# burn.net
KiCad netlist of a schematic drawn in EAGLE
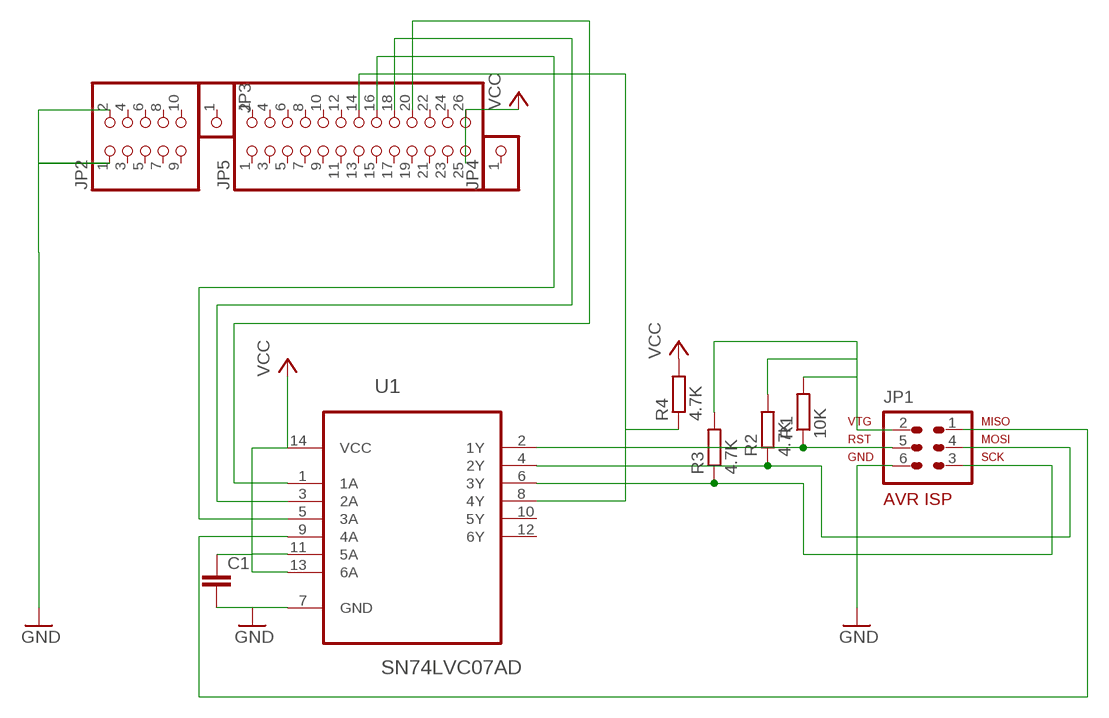
[diagram p0: schematic, sheet 1]

(export (version "E")
  (design (tool "Eeschema 10.0.6"))
  (components
    (comp (ref "C1")
      (value "C-EUC1206K")
      (footprint "eagle-import:C1206K")
      (libsource (lib "eagle-import") (part "C-EUC1206K"))
    )
    (comp (ref "JP1")
      (value "AVR-ISP")
      (footprint "eagle-import:AVR-ISP-6")
      (libsource (lib "eagle-import") (part "AVR-ISP-6"))
    )
    (comp (ref "JP2")
      (value "PINHD-2X5")
      (footprint "eagle-import:2X05")
      (libsource (lib "eagle-import") (part "PINHD-2X5"))
    )
    (comp (ref "JP3")
      (value "PINHD-1X1")
      (footprint "eagle-import:1X01")
      (libsource (lib "eagle-import") (part "PINHD-1X1"))
    )
    (comp (ref "JP4")
      (value "PINHD-1X1")
      (footprint "eagle-import:1X01")
      (libsource (lib "eagle-import") (part "PINHD-1X1"))
    )
    (comp (ref "JP5")
      (value "PINHD-2X13")
      (footprint "eagle-import:2X13")
      (libsource (lib "eagle-import") (part "PINHD-2X13"))
    )
    (comp (ref "R1")
      (value "10K")
      (footprint "eagle-import:R1206W")
      (libsource (lib "eagle-import") (part "R-EU_R1206W"))
    )
    (comp (ref "R2")
      (value "4.7K")
      (footprint "eagle-import:R1206W")
      (libsource (lib "eagle-import") (part "R-EU_R1206W"))
    )
    (comp (ref "R3")
      (value "4.7K")
      (footprint "eagle-import:R1206W")
      (libsource (lib "eagle-import") (part "R-EU_R1206W"))
    )
    (comp (ref "R4")
      (value "4.7K")
      (footprint "eagle-import:R1206W")
      (libsource (lib "eagle-import") (part "R-EU_R1206W"))
    )
    (comp (ref "U1")
      (value "SN74LVC07AD")
      (footprint "eagle-import:SOIC127P600X175-14N")
      (fields (field (name "MF") "Texas Instruments"))
      (libsource (lib "eagle-import") (part "SN74LVC07AD"))
    )
  )
  (nets
    (net (code "1") (name "GND") (class "Default")
      (node (ref "C1") (pin "2") (pinfunction "2_2") (pintype "passive"))
      (node (ref "JP1") (pin "6") (pinfunction "6_6") (pintype "passive"))
      (node (ref "JP2") (pin "1") (pinfunction "1_1") (pintype "passive"))
      (node (ref "JP2") (pin "2") (pinfunction "2_2") (pintype "passive"))
      (node (ref "U1") (pin "7") (pinfunction "GND_7") (pintype "passive"))
    )
    (net (code "2") (name "Net-(JP1-Pad2)") (class "Default")
      (node (ref "JP1") (pin "2") (pinfunction "2_2") (pintype "passive"))
      (node (ref "R1") (pin "2") (pinfunction "2_2") (pintype "passive"))
      (node (ref "R2") (pin "2") (pinfunction "2_2") (pintype "passive"))
      (node (ref "R3") (pin "2") (pinfunction "2_2") (pintype "passive"))
    )
    (net (code "3") (name "Net-(U1-1A)") (class "Default")
      (node (ref "JP5") (pin "20") (pinfunction "20_20") (pintype "passive"))
      (node (ref "U1") (pin "1") (pinfunction "1A_1") (pintype "input"))
    )
    (net (code "4") (name "Net-(U1-1Y)") (class "Default")
      (node (ref "JP1") (pin "5") (pinfunction "5_5") (pintype "passive"))
      (node (ref "R1") (pin "1") (pinfunction "1_1") (pintype "passive"))
      (node (ref "U1") (pin "2") (pinfunction "1Y_2") (pintype "output"))
    )
    (net (code "5") (name "Net-(U1-2A)") (class "Default")
      (node (ref "JP5") (pin "18") (pinfunction "18_18") (pintype "passive"))
      (node (ref "U1") (pin "3") (pinfunction "2A_3") (pintype "input"))
    )
    (net (code "6") (name "Net-(U1-2Y)") (class "Default")
      (node (ref "JP1") (pin "4") (pinfunction "4_4") (pintype "passive"))
      (node (ref "R2") (pin "1") (pinfunction "1_1") (pintype "passive"))
      (node (ref "U1") (pin "4") (pinfunction "2Y_4") (pintype "output"))
    )
    (net (code "7") (name "Net-(U1-3A)") (class "Default")
      (node (ref "JP5") (pin "16") (pinfunction "16_16") (pintype "passive"))
      (node (ref "U1") (pin "5") (pinfunction "3A_5") (pintype "input"))
    )
    (net (code "8") (name "Net-(U1-3Y)") (class "Default")
      (node (ref "JP1") (pin "3") (pinfunction "3_3") (pintype "passive"))
      (node (ref "R3") (pin "1") (pinfunction "1_1") (pintype "passive"))
      (node (ref "U1") (pin "6") (pinfunction "3Y_6") (pintype "output"))
    )
    (net (code "9") (name "Net-(U1-4A)") (class "Default")
      (node (ref "JP1") (pin "1") (pinfunction "1_1") (pintype "passive"))
      (node (ref "U1") (pin "9") (pinfunction "4A_9") (pintype "input"))
    )
    (net (code "10") (name "Net-(U1-4Y)") (class "Default")
      (node (ref "JP5") (pin "14") (pinfunction "14_14") (pintype "passive"))
      (node (ref "R4") (pin "1") (pinfunction "1_1") (pintype "passive"))
      (node (ref "U1") (pin "8") (pinfunction "4Y_8") (pintype "output"))
    )
    (net (code "11") (name "VCC") (class "Default")
      (node (ref "C1") (pin "1") (pinfunction "1_1") (pintype "passive"))
      (node (ref "JP5") (pin "25") (pinfunction "25_25") (pintype "passive"))
      (node (ref "JP5") (pin "26") (pinfunction "26_26") (pintype "passive"))
      (node (ref "R4") (pin "2") (pinfunction "2_2") (pintype "passive"))
      (node (ref "U1") (pin "11") (pinfunction "5A_11") (pintype "input"))
      (node (ref "U1") (pin "13") (pinfunction "6A_13") (pintype "input"))
      (node (ref "U1") (pin "14") (pinfunction "VCC_14") (pintype "power_in"))
    )
    (net (code "12") (name "unconnected-(JP2-Pad3)") (class "Default")
      (node (ref "JP2") (pin "3") (pinfunction "3_3") (pintype "passive"))
    )
    (net (code "13") (name "unconnected-(JP2-Pad4)") (class "Default")
      (node (ref "JP2") (pin "4") (pinfunction "4_4") (pintype "passive"))
    )
    (net (code "14") (name "unconnected-(JP2-Pad5)") (class "Default")
      (node (ref "JP2") (pin "5") (pinfunction "5_5") (pintype "passive"))
    )
    (net (code "15") (name "unconnected-(JP2-Pad6)") (class "Default")
      (node (ref "JP2") (pin "6") (pinfunction "6_6") (pintype "passive"))
    )
    (net (code "16") (name "unconnected-(JP2-Pad7)") (class "Default")
      (node (ref "JP2") (pin "7") (pinfunction "7_7") (pintype "passive"))
    )
    (net (code "17") (name "unconnected-(JP2-Pad8)") (class "Default")
      (node (ref "JP2") (pin "8") (pinfunction "8_8") (pintype "passive"))
    )
    (net (code "18") (name "unconnected-(JP2-Pad9)") (class "Default")
      (node (ref "JP2") (pin "9") (pinfunction "9_9") (pintype "passive"))
    )
    (net (code "19") (name "unconnected-(JP2-Pad10)") (class "Default")
      (node (ref "JP2") (pin "10") (pinfunction "10_10") (pintype "passive"))
    )
    (net (code "20") (name "unconnected-(JP3-Pad1)") (class "Default")
      (node (ref "JP3") (pin "1") (pinfunction "1_1") (pintype "passive"))
    )
    (net (code "21") (name "unconnected-(JP4-Pad1)") (class "Default")
      (node (ref "JP4") (pin "1") (pinfunction "1_1") (pintype "passive"))
    )
    (net (code "22") (name "unconnected-(JP5-Pad1)") (class "Default")
      (node (ref "JP5") (pin "1") (pinfunction "1_1") (pintype "passive"))
    )
    (net (code "23") (name "unconnected-(JP5-Pad2)") (class "Default")
      (node (ref "JP5") (pin "2") (pinfunction "2_2") (pintype "passive"))
    )
    (net (code "24") (name "unconnected-(JP5-Pad3)") (class "Default")
      (node (ref "JP5") (pin "3") (pinfunction "3_3") (pintype "passive"))
    )
    (net (code "25") (name "unconnected-(JP5-Pad4)") (class "Default")
      (node (ref "JP5") (pin "4") (pinfunction "4_4") (pintype "passive"))
    )
    (net (code "26") (name "unconnected-(JP5-Pad5)") (class "Default")
      (node (ref "JP5") (pin "5") (pinfunction "5_5") (pintype "passive"))
    )
    (net (code "27") (name "unconnected-(JP5-Pad6)") (class "Default")
      (node (ref "JP5") (pin "6") (pinfunction "6_6") (pintype "passive"))
    )
    (net (code "28") (name "unconnected-(JP5-Pad7)") (class "Default")
      (node (ref "JP5") (pin "7") (pinfunction "7_7") (pintype "passive"))
    )
    (net (code "29") (name "unconnected-(JP5-Pad8)") (class "Default")
      (node (ref "JP5") (pin "8") (pinfunction "8_8") (pintype "passive"))
    )
    (net (code "30") (name "unconnected-(JP5-Pad9)") (class "Default")
      (node (ref "JP5") (pin "9") (pinfunction "9_9") (pintype "passive"))
    )
    (net (code "31") (name "unconnected-(JP5-Pad10)") (class "Default")
      (node (ref "JP5") (pin "10") (pinfunction "10_10") (pintype "passive"))
    )
    (net (code "32") (name "unconnected-(JP5-Pad11)") (class "Default")
      (node (ref "JP5") (pin "11") (pinfunction "11_11") (pintype "passive"))
    )
    (net (code "33") (name "unconnected-(JP5-Pad12)") (class "Default")
      (node (ref "JP5") (pin "12") (pinfunction "12_12") (pintype "passive"))
    )
    (net (code "34") (name "unconnected-(JP5-Pad13)") (class "Default")
      (node (ref "JP5") (pin "13") (pinfunction "13_13") (pintype "passive"))
    )
    (net (code "35") (name "unconnected-(JP5-Pad15)") (class "Default")
      (node (ref "JP5") (pin "15") (pinfunction "15_15") (pintype "passive"))
    )
    (net (code "36") (name "unconnected-(JP5-Pad17)") (class "Default")
      (node (ref "JP5") (pin "17") (pinfunction "17_17") (pintype "passive"))
    )
    (net (code "37") (name "unconnected-(JP5-Pad19)") (class "Default")
      (node (ref "JP5") (pin "19") (pinfunction "19_19") (pintype "passive"))
    )
    (net (code "38") (name "unconnected-(JP5-Pad21)") (class "Default")
      (node (ref "JP5") (pin "21") (pinfunction "21_21") (pintype "passive"))
    )
    (net (code "39") (name "unconnected-(JP5-Pad22)") (class "Default")
      (node (ref "JP5") (pin "22") (pinfunction "22_22") (pintype "passive"))
    )
    (net (code "40") (name "unconnected-(JP5-Pad23)") (class "Default")
      (node (ref "JP5") (pin "23") (pinfunction "23_23") (pintype "passive"))
    )
    (net (code "41") (name "unconnected-(JP5-Pad24)") (class "Default")
      (node (ref "JP5") (pin "24") (pinfunction "24_24") (pintype "passive"))
    )
    (net (code "42") (name "unconnected-(U1-5Y-Pad10)") (class "Default")
      (node (ref "U1") (pin "10") (pinfunction "5Y_10") (pintype "output"))
    )
    (net (code "43") (name "unconnected-(U1-6Y-Pad12)") (class "Default")
      (node (ref "U1") (pin "12") (pinfunction "6Y_12") (pintype "output"))
    )
  )
)
